# TARGET_xDOT.net
KiCad netlist of a schematic drawn in EAGLE
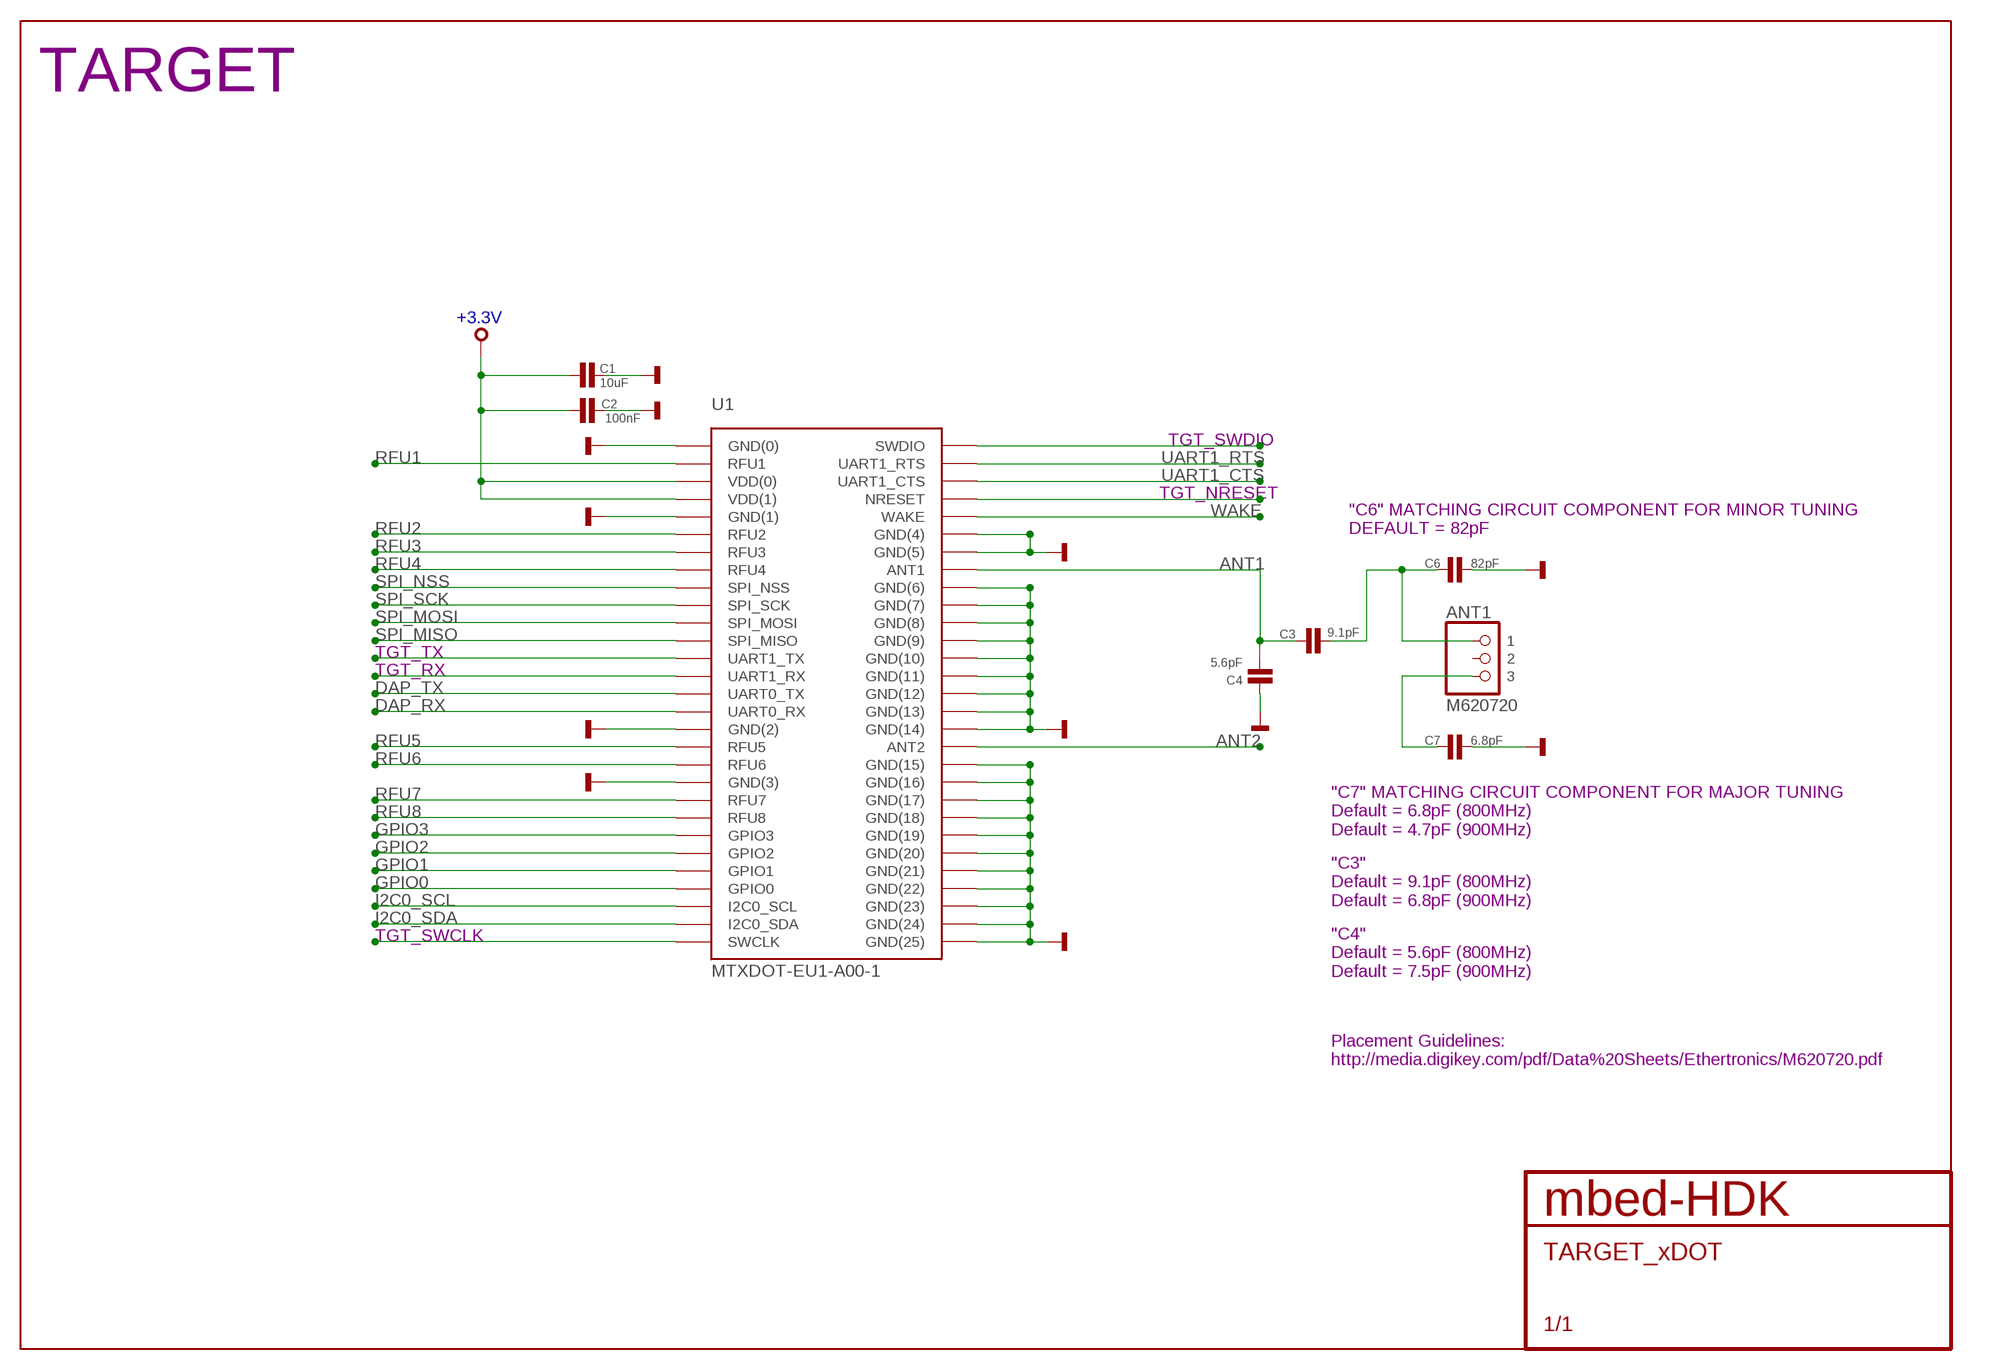
[diagram p0: schematic, sheet 1]

(export (version "E")
  (design (tool "Eeschema 10.0.6"))
  (components
    (comp (ref "ANT1")
      (value "M620720")
      (footprint "eagle-import:M620720")
      (fields (field (name "MF") "Ethertronics"))
      (libsource (lib "eagle-import") (part "M620720"))
    )
    (comp (ref "C1")
      (value "10uF")
      (footprint "eagle-import:0603")
      (libsource (lib "eagle-import") (part "CAPACITOR0603"))
    )
    (comp (ref "C2")
      (value "100nF")
      (footprint "eagle-import:0603")
      (libsource (lib "eagle-import") (part "CAPACITOR0603"))
    )
    (comp (ref "C3")
      (value "9.1pF")
      (footprint "eagle-import:0402")
      (libsource (lib "eagle-import") (part "CAPACITOR0402"))
    )
    (comp (ref "C4")
      (value "5.6pF")
      (footprint "eagle-import:0402")
      (libsource (lib "eagle-import") (part "CAPACITOR0402"))
    )
    (comp (ref "C6")
      (value "82pF")
      (footprint "eagle-import:0402")
      (libsource (lib "eagle-import") (part "CAPACITOR0402"))
    )
    (comp (ref "C7")
      (value "6.8pF")
      (footprint "eagle-import:0402")
      (libsource (lib "eagle-import") (part "CAPACITOR0402"))
    )
    (comp (ref "U1")
      (value "MTXDOT-EU1-A00-1")
      (footprint "eagle-import:MTXDOT-EU1_NA1-A00-1")
      (fields (field (name "MF") "Multi-Tech Systems Inc."))
      (libsource (lib "eagle-import") (part "MTXDOT-EU1-A00-1"))
    )
  )
  (nets
    (net (code "1") (name "+3.3V") (class "Default")
      (node (ref "C1") (pin "1") (pinfunction "P$1_1") (pintype "passive"))
      (node (ref "C2") (pin "1") (pinfunction "P$1_1") (pintype "passive"))
      (node (ref "U1") (pin "P$3") (pinfunction "VDD(0)_P$3") (pintype "bidirectional"))
      (node (ref "U1") (pin "P$4") (pinfunction "VDD(1)_P$4") (pintype "bidirectional"))
    )
    (net (code "2") (name "/ANT1") (class "Default")
      (node (ref "C3") (pin "1") (pinfunction "P$1_1") (pintype "passive"))
      (node (ref "C4") (pin "2") (pinfunction "P$2_2") (pintype "passive"))
      (node (ref "U1") (pin "P$37") (pinfunction "ANT1_P$37") (pintype "bidirectional"))
    )
    (net (code "3") (name "/ANT2") (class "Default")
      (node (ref "U1") (pin "P$47") (pinfunction "ANT2_P$47") (pintype "bidirectional"))
    )
    (net (code "4") (name "/DAP_RX") (class "Default")
      (node (ref "U1") (pin "P$16") (pinfunction "UART0_RX_P$16") (pintype "bidirectional"))
    )
    (net (code "5") (name "/DAP_TX") (class "Default")
      (node (ref "U1") (pin "P$15") (pinfunction "UART0_TX_P$15") (pintype "bidirectional"))
    )
    (net (code "6") (name "/GPIO0") (class "Default")
      (node (ref "U1") (pin "P$26") (pinfunction "GPIO0_P$26") (pintype "bidirectional"))
    )
    (net (code "7") (name "/GPIO1") (class "Default")
      (node (ref "U1") (pin "P$25") (pinfunction "GPIO1_P$25") (pintype "bidirectional"))
    )
    (net (code "8") (name "/GPIO2") (class "Default")
      (node (ref "U1") (pin "P$24") (pinfunction "GPIO2_P$24") (pintype "bidirectional"))
    )
    (net (code "9") (name "/GPIO3") (class "Default")
      (node (ref "U1") (pin "P$23") (pinfunction "GPIO3_P$23") (pintype "bidirectional"))
    )
    (net (code "10") (name "/I2C0_SCL") (class "Default")
      (node (ref "U1") (pin "P$27") (pinfunction "I2C0_SCL_P$27") (pintype "bidirectional"))
    )
    (net (code "11") (name "/I2C0_SDA") (class "Default")
      (node (ref "U1") (pin "P$28") (pinfunction "I2C0_SDA_P$28") (pintype "bidirectional"))
    )
    (net (code "12") (name "/RFU1") (class "Default")
      (node (ref "U1") (pin "P$2") (pinfunction "RFU1_P$2") (pintype "bidirectional"))
    )
    (net (code "13") (name "/RFU2") (class "Default")
      (node (ref "U1") (pin "P$6") (pinfunction "RFU2_P$6") (pintype "bidirectional"))
    )
    (net (code "14") (name "/RFU3") (class "Default")
      (node (ref "U1") (pin "P$7") (pinfunction "RFU3_P$7") (pintype "bidirectional"))
    )
    (net (code "15") (name "/RFU4") (class "Default")
      (node (ref "U1") (pin "P$8") (pinfunction "RFU4_P$8") (pintype "bidirectional"))
    )
    (net (code "16") (name "/RFU5") (class "Default")
      (node (ref "U1") (pin "P$18") (pinfunction "RFU5_P$18") (pintype "bidirectional"))
    )
    (net (code "17") (name "/RFU6") (class "Default")
      (node (ref "U1") (pin "P$19") (pinfunction "RFU6_P$19") (pintype "bidirectional"))
    )
    (net (code "18") (name "/RFU7") (class "Default")
      (node (ref "U1") (pin "P$21") (pinfunction "RFU7_P$21") (pintype "bidirectional"))
    )
    (net (code "19") (name "/RFU8") (class "Default")
      (node (ref "U1") (pin "P$22") (pinfunction "RFU8_P$22") (pintype "bidirectional"))
    )
    (net (code "20") (name "/SPI_MISO") (class "Default")
      (node (ref "U1") (pin "P$12") (pinfunction "SPI_MISO_P$12") (pintype "bidirectional"))
    )
    (net (code "21") (name "/SPI_MOSI") (class "Default")
      (node (ref "U1") (pin "P$11") (pinfunction "SPI_MOSI_P$11") (pintype "bidirectional"))
    )
    (net (code "22") (name "/SPI_NSS") (class "Default")
      (node (ref "U1") (pin "P$9") (pinfunction "SPI_NSS_P$9") (pintype "bidirectional"))
    )
    (net (code "23") (name "/SPI_SCK") (class "Default")
      (node (ref "U1") (pin "P$10") (pinfunction "SPI_SCK_P$10") (pintype "bidirectional"))
    )
    (net (code "24") (name "/TGT_NRESET") (class "Default")
      (node (ref "U1") (pin "P$33") (pinfunction "NRESET_P$33") (pintype "bidirectional"))
    )
    (net (code "25") (name "/TGT_RX") (class "Default")
      (node (ref "U1") (pin "P$14") (pinfunction "UART1_RX_P$14") (pintype "bidirectional"))
    )
    (net (code "26") (name "/TGT_SWCLK") (class "Default")
      (node (ref "U1") (pin "P$29") (pinfunction "SWCLK_P$29") (pintype "bidirectional"))
    )
    (net (code "27") (name "/TGT_SWDIO") (class "Default")
      (node (ref "U1") (pin "P$30") (pinfunction "SWDIO_P$30") (pintype "bidirectional"))
    )
    (net (code "28") (name "/TGT_TX") (class "Default")
      (node (ref "U1") (pin "P$13") (pinfunction "UART1_TX_P$13") (pintype "bidirectional"))
    )
    (net (code "29") (name "/UART1_CTS") (class "Default")
      (node (ref "U1") (pin "P$32") (pinfunction "UART1_CTS_P$32") (pintype "bidirectional"))
    )
    (net (code "30") (name "/UART1_RTS") (class "Default")
      (node (ref "U1") (pin "P$31") (pinfunction "UART1_RTS_P$31") (pintype "bidirectional"))
    )
    (net (code "31") (name "/WAKE") (class "Default")
      (node (ref "U1") (pin "P$34") (pinfunction "WAKE_P$34") (pintype "bidirectional"))
    )
    (net (code "32") (name "GND") (class "Default")
      (node (ref "C1") (pin "2") (pinfunction "P$2_2") (pintype "passive"))
      (node (ref "C2") (pin "2") (pinfunction "P$2_2") (pintype "passive"))
      (node (ref "C4") (pin "1") (pinfunction "P$1_1") (pintype "passive"))
      (node (ref "C6") (pin "1") (pinfunction "P$1_1") (pintype "passive"))
      (node (ref "C7") (pin "1") (pinfunction "P$1_1") (pintype "passive"))
      (node (ref "U1") (pin "P$1") (pinfunction "GND(0)_P$1") (pintype "bidirectional"))
      (node (ref "U1") (pin "P$17") (pinfunction "GND(2)_P$17") (pintype "bidirectional"))
      (node (ref "U1") (pin "P$20") (pinfunction "GND(3)_P$20") (pintype "bidirectional"))
      (node (ref "U1") (pin "P$35") (pinfunction "GND(4)_P$35") (pintype "bidirectional"))
      (node (ref "U1") (pin "P$36") (pinfunction "GND(5)_P$36") (pintype "bidirectional"))
      (node (ref "U1") (pin "P$38") (pinfunction "GND(6)_P$38") (pintype "bidirectional"))
      (node (ref "U1") (pin "P$39") (pinfunction "GND(7)_P$39") (pintype "bidirectional"))
      (node (ref "U1") (pin "P$40") (pinfunction "GND(8)_P$40") (pintype "bidirectional"))
      (node (ref "U1") (pin "P$41") (pinfunction "GND(9)_P$41") (pintype "bidirectional"))
      (node (ref "U1") (pin "P$42") (pinfunction "GND(10)_P$42") (pintype "bidirectional"))
      (node (ref "U1") (pin "P$43") (pinfunction "GND(11)_P$43") (pintype "bidirectional"))
      (node (ref "U1") (pin "P$44") (pinfunction "GND(12)_P$44") (pintype "bidirectional"))
      (node (ref "U1") (pin "P$45") (pinfunction "GND(13)_P$45") (pintype "bidirectional"))
      (node (ref "U1") (pin "P$46") (pinfunction "GND(14)_P$46") (pintype "bidirectional"))
      (node (ref "U1") (pin "P$48") (pinfunction "GND(15)_P$48") (pintype "bidirectional"))
      (node (ref "U1") (pin "P$49") (pinfunction "GND(16)_P$49") (pintype "bidirectional"))
      (node (ref "U1") (pin "P$5") (pinfunction "GND(1)_P$5") (pintype "bidirectional"))
      (node (ref "U1") (pin "P$50") (pinfunction "GND(17)_P$50") (pintype "bidirectional"))
      (node (ref "U1") (pin "P$51") (pinfunction "GND(18)_P$51") (pintype "bidirectional"))
      (node (ref "U1") (pin "P$52") (pinfunction "GND(19)_P$52") (pintype "bidirectional"))
      (node (ref "U1") (pin "P$53") (pinfunction "GND(20)_P$53") (pintype "bidirectional"))
      (node (ref "U1") (pin "P$54") (pinfunction "GND(21)_P$54") (pintype "bidirectional"))
      (node (ref "U1") (pin "P$55") (pinfunction "GND(22)_P$55") (pintype "bidirectional"))
      (node (ref "U1") (pin "P$56") (pinfunction "GND(23)_P$56") (pintype "bidirectional"))
      (node (ref "U1") (pin "P$57") (pinfunction "GND(24)_P$57") (pintype "bidirectional"))
      (node (ref "U1") (pin "P$58") (pinfunction "GND(25)_P$58") (pintype "bidirectional"))
    )
    (net (code "33") (name "Net-(ANT1-1)") (class "Default")
      (node (ref "ANT1") (pin "P$1") (pinfunction "1_P$1") (pintype "passive"))
      (node (ref "C3") (pin "2") (pinfunction "P$2_2") (pintype "passive"))
      (node (ref "C6") (pin "2") (pinfunction "P$2_2") (pintype "passive"))
    )
    (net (code "34") (name "Net-(ANT1-3)") (class "Default")
      (node (ref "ANT1") (pin "P$3") (pinfunction "3_P$3") (pintype "passive"))
      (node (ref "C7") (pin "2") (pinfunction "P$2_2") (pintype "passive"))
    )
    (net (code "35") (name "unconnected-(ANT1-2-PadP$2)") (class "Default")
      (node (ref "ANT1") (pin "P$2") (pinfunction "2_P$2") (pintype "passive"))
    )
  )
)
